# grid_display.net
KiCad netlist of a schematic drawn in EasyEDA
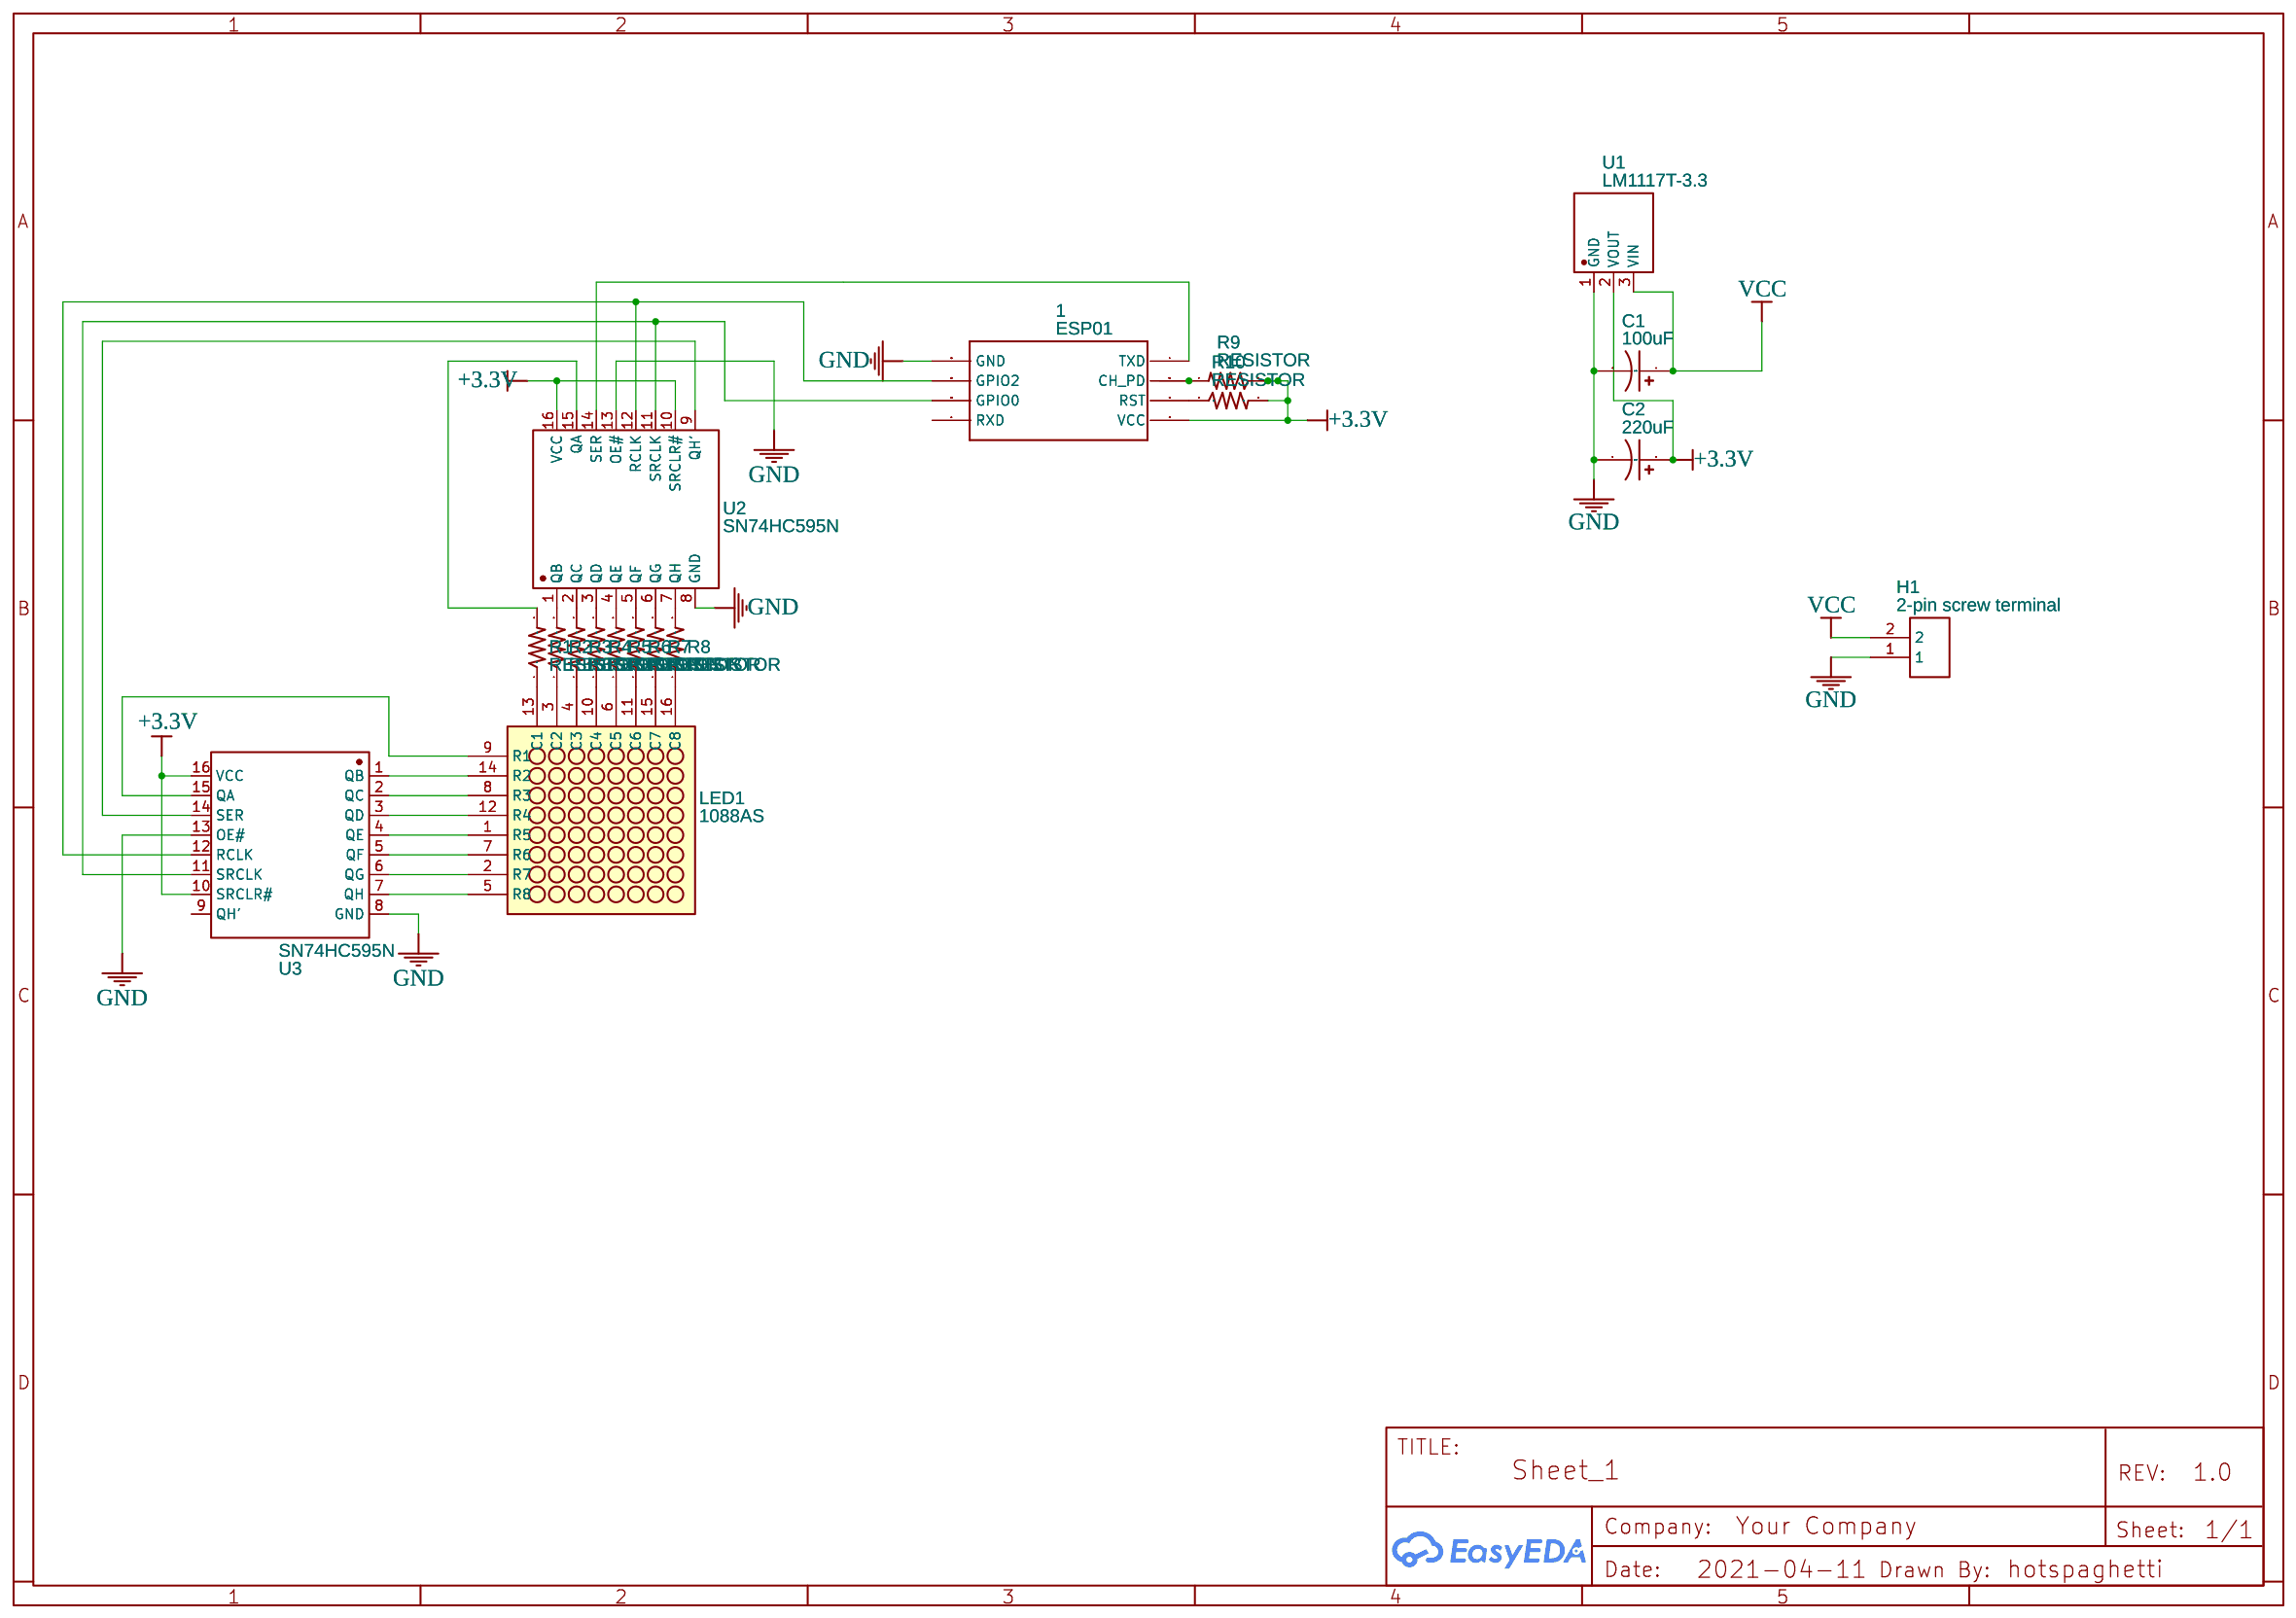
[diagram p0: schematic sheet]

(export (version "E")
  (design (tool "Eeschema 10.0.6"))
  (components
    (comp (ref "1") (value "ESP01") (libsource (lib "") (part "ESP01")))
    (comp (ref "C1") (value "100uF") (libsource (lib "") (part "CE_TH_D10.0×F5.0_US")))
    (comp (ref "C2") (value "220uF") (libsource (lib "") (part "CE_TH_D10.0×F5.0_US")))
    (comp (ref "H1") (value "2-pin screw terminal") (libsource (lib "") (part "2-pin screw terminal")))
    (comp (ref "LED1")
      (value "1088AS")
      (fields
        (field (name "BOM_Manufacturer Part") "8X8LEDLED dots 3.0mmPoint path red")
        (field (name "BOM_Supplier Part") "C10524")
      )
      (libsource (lib "") (part "1088AS"))
    )
    (comp (ref "R1") (value "RESISTOR") (libsource (lib "") (part "RESISTOR_1")))
    (comp (ref "R2") (value "RESISTOR") (libsource (lib "") (part "RESISTOR_1")))
    (comp (ref "R3") (value "RESISTOR") (libsource (lib "") (part "RESISTOR_1")))
    (comp (ref "R4") (value "RESISTOR") (libsource (lib "") (part "RESISTOR_1")))
    (comp (ref "R5") (value "RESISTOR") (libsource (lib "") (part "RESISTOR_1")))
    (comp (ref "R6") (value "RESISTOR") (libsource (lib "") (part "RESISTOR_1")))
    (comp (ref "R7") (value "RESISTOR") (libsource (lib "") (part "RESISTOR_1")))
    (comp (ref "R8") (value "RESISTOR") (libsource (lib "") (part "RESISTOR_1")))
    (comp (ref "R9") (value "RESISTOR") (libsource (lib "") (part "RESISTOR")))
    (comp (ref "R10") (value "RESISTOR") (libsource (lib "") (part "RESISTOR_2")))
    (comp (ref "U1")
      (value "LM1117T-3.3")
      (fields (field (name "BOM_Supplier Part") "C498321"))
      (libsource (lib "") (part "LM1117T-3.3"))
    )
    (comp (ref "U2")
      (value "SN74HC595N")
      (fields (field (name "BOM_Supplier Part") "C78711"))
      (libsource (lib "") (part "SN74HC595N_1"))
    )
    (comp (ref "U3")
      (value "SN74HC595N")
      (fields (field (name "BOM_Supplier Part") "C78711"))
      (libsource (lib "") (part "SN74HC595N"))
    )
  )
  (nets
    (net (code "1") (name "+3.3V") (class "Default")
      (node (ref "1") (pin "VCC") (pinfunction "VCC_VCC") (pintype "bidirectional"))
      (node (ref "C2") (pin "1") (pinfunction "1_1") (pintype "unspecified"))
      (node (ref "R10") (pin "2") (pinfunction "2_2") (pintype "unspecified"))
      (node (ref "R9") (pin "1") (pinfunction "1_1") (pintype "unspecified"))
      (node (ref "U1") (pin "2") (pinfunction "VOUT_2") (pintype "unspecified"))
      (node (ref "U2") (pin "10") (pinfunction "SRCLR#_10") (pintype "unspecified"))
      (node (ref "U2") (pin "16") (pinfunction "VCC_16") (pintype "unspecified"))
      (node (ref "U3") (pin "10") (pinfunction "SRCLR#_10") (pintype "unspecified"))
      (node (ref "U3") (pin "16") (pinfunction "VCC_16") (pintype "unspecified"))
    )
    (net (code "2") (name "GND") (class "Default")
      (node (ref "1") (pin "GND") (pinfunction "GND_GND") (pintype "bidirectional"))
      (node (ref "C1") (pin "2") (pinfunction "2_2") (pintype "unspecified"))
      (node (ref "C2") (pin "2") (pinfunction "2_2") (pintype "unspecified"))
      (node (ref "H1") (pin "1") (pinfunction "1_1") (pintype "unspecified"))
      (node (ref "U1") (pin "1") (pinfunction "GND_1") (pintype "unspecified"))
      (node (ref "U2") (pin "13") (pinfunction "OE#_13") (pintype "unspecified"))
      (node (ref "U2") (pin "8") (pinfunction "GND_8") (pintype "unspecified"))
      (node (ref "U3") (pin "13") (pinfunction "OE#_13") (pintype "unspecified"))
      (node (ref "U3") (pin "8") (pinfunction "GND_8") (pintype "unspecified"))
    )
    (net (code "3") (name "Net-(1-PadCH_PD)") (class "Default")
      (node (ref "1") (pin "CH_PD") (pinfunction "CH_PD_CH_PD") (pintype "bidirectional"))
      (node (ref "R9") (pin "2") (pinfunction "2_2") (pintype "unspecified"))
    )
    (net (code "4") (name "Net-(1-PadRST)") (class "Default")
      (node (ref "1") (pin "RST") (pinfunction "RST_RST") (pintype "bidirectional"))
      (node (ref "R10") (pin "1") (pinfunction "1_1") (pintype "unspecified"))
    )
    (net (code "5") (name "Net-(1-TXD)") (class "Default")
      (node (ref "1") (pin "TX") (pinfunction "TXD_TX") (pintype "bidirectional"))
      (node (ref "U2") (pin "14") (pinfunction "SER_14") (pintype "unspecified"))
    )
    (net (code "6") (name "Net-(LED1-C1)") (class "Default")
      (node (ref "LED1") (pin "13") (pinfunction "C1_13") (pintype "unspecified"))
      (node (ref "R1") (pin "1") (pinfunction "1_1") (pintype "unspecified"))
    )
    (net (code "7") (name "Net-(LED1-C2)") (class "Default")
      (node (ref "LED1") (pin "3") (pinfunction "C2_3") (pintype "unspecified"))
      (node (ref "R2") (pin "1") (pinfunction "1_1") (pintype "unspecified"))
    )
    (net (code "8") (name "Net-(LED1-C3)") (class "Default")
      (node (ref "LED1") (pin "4") (pinfunction "C3_4") (pintype "unspecified"))
      (node (ref "R3") (pin "1") (pinfunction "1_1") (pintype "unspecified"))
    )
    (net (code "9") (name "Net-(LED1-C4)") (class "Default")
      (node (ref "LED1") (pin "10") (pinfunction "C4_10") (pintype "unspecified"))
      (node (ref "R4") (pin "1") (pinfunction "1_1") (pintype "unspecified"))
    )
    (net (code "10") (name "Net-(LED1-C5)") (class "Default")
      (node (ref "LED1") (pin "6") (pinfunction "C5_6") (pintype "unspecified"))
      (node (ref "R5") (pin "1") (pinfunction "1_1") (pintype "unspecified"))
    )
    (net (code "11") (name "Net-(LED1-C6)") (class "Default")
      (node (ref "LED1") (pin "11") (pinfunction "C6_11") (pintype "unspecified"))
      (node (ref "R6") (pin "1") (pinfunction "1_1") (pintype "unspecified"))
    )
    (net (code "12") (name "Net-(LED1-C7)") (class "Default")
      (node (ref "LED1") (pin "15") (pinfunction "C7_15") (pintype "unspecified"))
      (node (ref "R7") (pin "1") (pinfunction "1_1") (pintype "unspecified"))
    )
    (net (code "13") (name "Net-(LED1-C8)") (class "Default")
      (node (ref "LED1") (pin "16") (pinfunction "C8_16") (pintype "unspecified"))
      (node (ref "R8") (pin "1") (pinfunction "1_1") (pintype "unspecified"))
    )
    (net (code "14") (name "Net-(LED1-R1)") (class "Default")
      (node (ref "LED1") (pin "9") (pinfunction "R1_9") (pintype "unspecified"))
      (node (ref "U3") (pin "15") (pinfunction "QA_15") (pintype "unspecified"))
    )
    (net (code "15") (name "Net-(LED1-R2)") (class "Default")
      (node (ref "LED1") (pin "14") (pinfunction "R2_14") (pintype "unspecified"))
      (node (ref "U3") (pin "1") (pinfunction "QB_1") (pintype "unspecified"))
    )
    (net (code "16") (name "Net-(LED1-R3)") (class "Default")
      (node (ref "LED1") (pin "8") (pinfunction "R3_8") (pintype "unspecified"))
      (node (ref "U3") (pin "2") (pinfunction "QC_2") (pintype "unspecified"))
    )
    (net (code "17") (name "Net-(LED1-R4)") (class "Default")
      (node (ref "LED1") (pin "12") (pinfunction "R4_12") (pintype "unspecified"))
      (node (ref "U3") (pin "3") (pinfunction "QD_3") (pintype "unspecified"))
    )
    (net (code "18") (name "Net-(LED1-R5)") (class "Default")
      (node (ref "LED1") (pin "1") (pinfunction "R5_1") (pintype "unspecified"))
      (node (ref "U3") (pin "4") (pinfunction "QE_4") (pintype "unspecified"))
    )
    (net (code "19") (name "Net-(LED1-R6)") (class "Default")
      (node (ref "LED1") (pin "7") (pinfunction "R6_7") (pintype "unspecified"))
      (node (ref "U3") (pin "5") (pinfunction "QF_5") (pintype "unspecified"))
    )
    (net (code "20") (name "Net-(LED1-R7)") (class "Default")
      (node (ref "LED1") (pin "2") (pinfunction "R7_2") (pintype "unspecified"))
      (node (ref "U3") (pin "6") (pinfunction "QG_6") (pintype "unspecified"))
    )
    (net (code "21") (name "Net-(LED1-R8)") (class "Default")
      (node (ref "LED1") (pin "5") (pinfunction "R8_5") (pintype "unspecified"))
      (node (ref "U3") (pin "7") (pinfunction "QH_7") (pintype "unspecified"))
    )
    (net (code "22") (name "Net-(U2-QA)") (class "Default")
      (node (ref "R1") (pin "2") (pinfunction "2_2") (pintype "unspecified"))
      (node (ref "U2") (pin "15") (pinfunction "QA_15") (pintype "unspecified"))
    )
    (net (code "23") (name "Net-(U2-QB)") (class "Default")
      (node (ref "R2") (pin "2") (pinfunction "2_2") (pintype "unspecified"))
      (node (ref "U2") (pin "1") (pinfunction "QB_1") (pintype "unspecified"))
    )
    (net (code "24") (name "Net-(U2-QC)") (class "Default")
      (node (ref "R3") (pin "2") (pinfunction "2_2") (pintype "unspecified"))
      (node (ref "U2") (pin "2") (pinfunction "QC_2") (pintype "unspecified"))
    )
    (net (code "25") (name "Net-(U2-QD)") (class "Default")
      (node (ref "R4") (pin "2") (pinfunction "2_2") (pintype "unspecified"))
      (node (ref "U2") (pin "3") (pinfunction "QD_3") (pintype "unspecified"))
    )
    (net (code "26") (name "Net-(U2-QE)") (class "Default")
      (node (ref "R5") (pin "2") (pinfunction "2_2") (pintype "unspecified"))
      (node (ref "U2") (pin "4") (pinfunction "QE_4") (pintype "unspecified"))
    )
    (net (code "27") (name "Net-(U2-QF)") (class "Default")
      (node (ref "R6") (pin "2") (pinfunction "2_2") (pintype "unspecified"))
      (node (ref "U2") (pin "5") (pinfunction "QF_5") (pintype "unspecified"))
    )
    (net (code "28") (name "Net-(U2-QG)") (class "Default")
      (node (ref "R7") (pin "2") (pinfunction "2_2") (pintype "unspecified"))
      (node (ref "U2") (pin "6") (pinfunction "QG_6") (pintype "unspecified"))
    )
    (net (code "29") (name "Net-(U2-QH')") (class "Default")
      (node (ref "U2") (pin "9") (pinfunction "QH'_9") (pintype "unspecified"))
      (node (ref "U3") (pin "14") (pinfunction "SER_14") (pintype "unspecified"))
    )
    (net (code "30") (name "Net-(U2-QH)") (class "Default")
      (node (ref "R8") (pin "2") (pinfunction "2_2") (pintype "unspecified"))
      (node (ref "U2") (pin "7") (pinfunction "QH_7") (pintype "unspecified"))
    )
    (net (code "31") (name "Net-(U2-RCLK)") (class "Default")
      (node (ref "1") (pin "GPIO2") (pinfunction "GPIO2_GPIO2") (pintype "bidirectional"))
      (node (ref "U2") (pin "12") (pinfunction "RCLK_12") (pintype "unspecified"))
      (node (ref "U3") (pin "12") (pinfunction "RCLK_12") (pintype "unspecified"))
    )
    (net (code "32") (name "Net-(U2-SRCLK)") (class "Default")
      (node (ref "1") (pin "GPIO0") (pinfunction "GPIO0_GPIO0") (pintype "bidirectional"))
      (node (ref "U2") (pin "11") (pinfunction "SRCLK_11") (pintype "unspecified"))
      (node (ref "U3") (pin "11") (pinfunction "SRCLK_11") (pintype "unspecified"))
    )
    (net (code "33") (name "VCC") (class "Default")
      (node (ref "C1") (pin "1") (pinfunction "1_1") (pintype "unspecified"))
      (node (ref "H1") (pin "2") (pinfunction "2_2") (pintype "unspecified"))
      (node (ref "U1") (pin "3") (pinfunction "VIN_3") (pintype "unspecified"))
    )
    (net (code "34") (name "unconnected-(1-RXD-PadRX)") (class "Default")
      (node (ref "1") (pin "RX") (pinfunction "RXD_RX") (pintype "bidirectional"))
    )
    (net (code "35") (name "unconnected-(U3-QH'-Pad9)") (class "Default")
      (node (ref "U3") (pin "9") (pinfunction "QH'_9") (pintype "unspecified"))
    )
  )
)
